# Copy_of_Archimedes_Islemci_Kat.net
KiCad netlist of a schematic drawn in Altium Designer
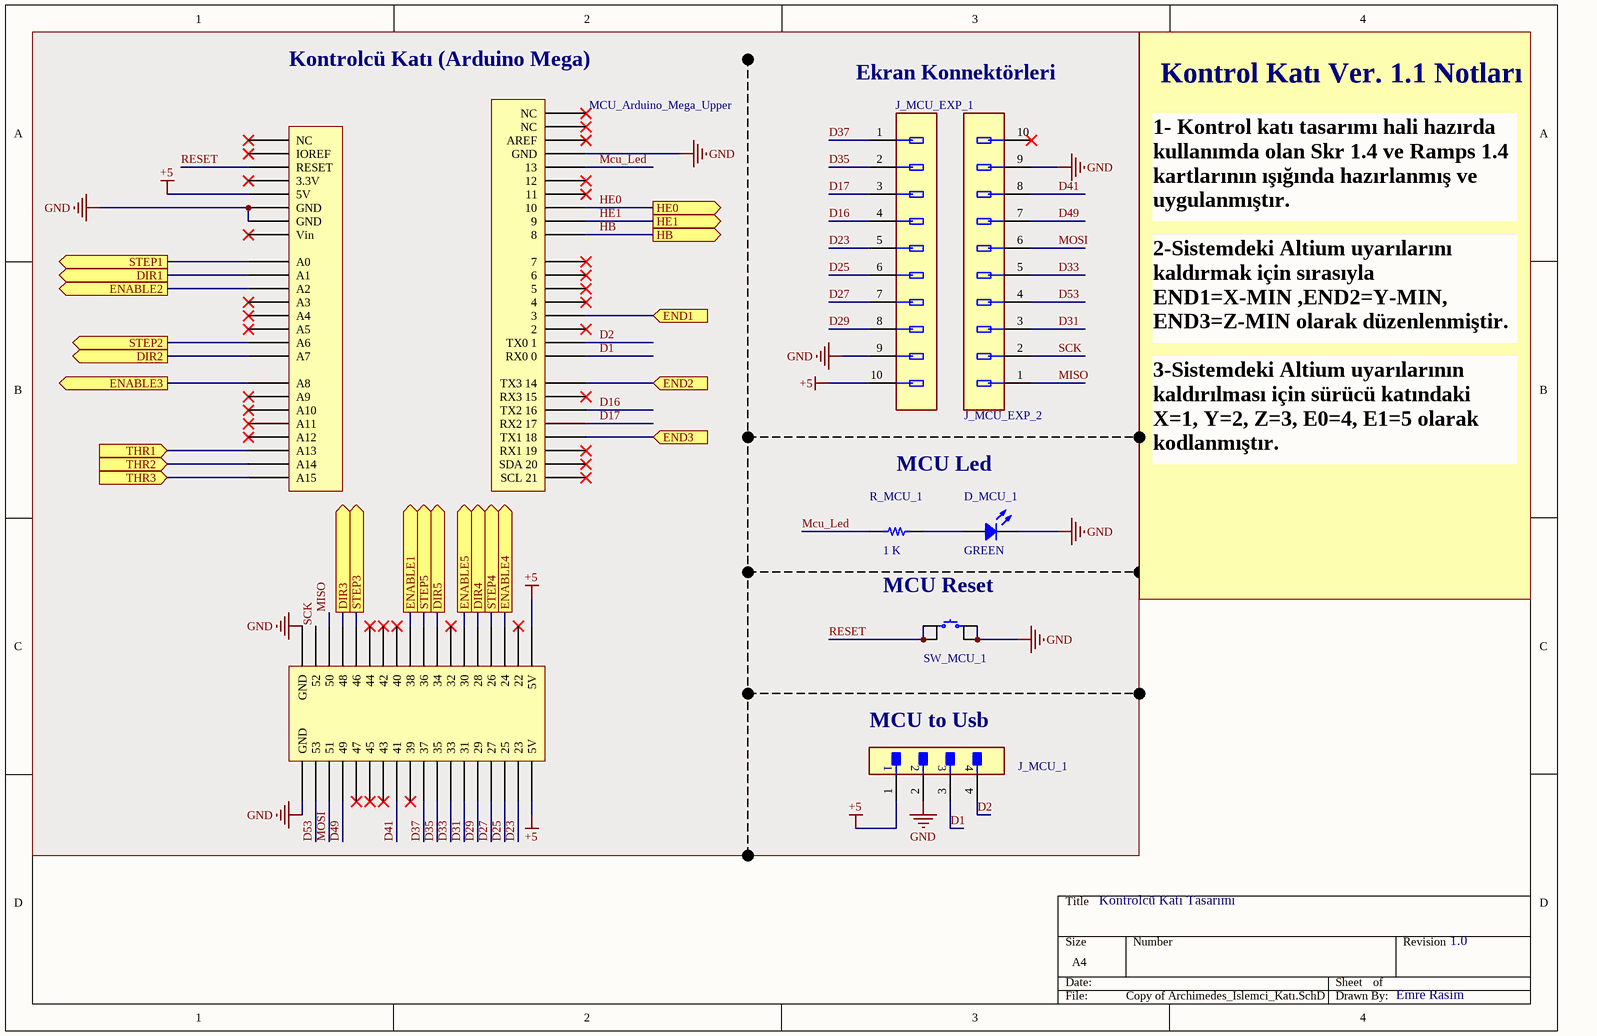
[diagram p0: Copy of Archimedes_Islemci_Katı.SchDoc]

(export (version "E")
  (design (tool "Eeschema 10.0.6"))
  (components
    (comp (ref "D_MCU_1")
      (value "GREEN")
      (footprint "LED 0805/2012 GREEN")
      (description "LED 805")
      (libsource (lib "Pasifler") (part "LED 805"))
    )
    (comp (ref "J_MCU_1")
      (value "2.5 mm locked")
      (footprint "CON_2.5MM_4_LEAD_180_LOCKED")
      (description "2.5 mm 4 lead locked connector")
      (libsource (lib "EKIM_Team_Main") (part "Con_2.5mm_4_lead_180_locked"))
    )
    (comp (ref "J_MCU_EXP_1")
      (value "Con_2.54mm_10 lead_2 row_Ipc connector")
      (footprint "Con_10pin_2row_ıpc_connector")
      (description "CONN 10 Positions Header Connector 0.100\" (2.54mm) Through Hole Gold")
      (fields (field (name "VOLTAGE") "250V") (field (name "MANUFACTURER") "Molex"))
      (libsource (lib "EKIM_Team_Main") (part "Con_2.54mm_10 lead_2 row_Ipc connector"))
    )
    (comp (ref "J_MCU_EXP_2")
      (value "Con_2.54mm_10 lead_2 row_Ipc connector")
      (footprint "Con_10pin_2row_ıpc_connector")
      (description "CONN 10 Positions Header Connector 0.100\" (2.54mm) Through Hole Gold")
      (fields (field (name "VOLTAGE") "250V") (field (name "MANUFACTURER") "Molex"))
      (libsource (lib "") (part "Con_2.54mm_10 lead_2 row_Ipc connector_1"))
    )
    (comp (ref "MCU_Arduino_Mega_Upper")
      (value "Arduino Mega 2560")
      (footprint "MCU_Arduino_MEGA_Upper")
      (libsource (lib "EKIM_Team_Main") (part "MCU_Arduino_Mega_Upper"))
    )
    (comp (ref "R_MCU_1")
      (value "1 K")
      (footprint "RES 0805/2012")
      (description "Resistor 805")
      (libsource (lib "Pasifler") (part "Resistor 805"))
    )
    (comp (ref "SW_MCU_1")
      (value "Push button with 6x6 landmark")
      (footprint "SW_PUSH_6X6mm")
      (libsource (lib "EKIM_Team_Main") (part "SW_PUSH_6X6mm"))
    )
  )
  (nets
    (net (code "1") (name "+5") (class "Default")
      (node (ref "J_MCU_1") (pin "1") (pinfunction "1_1") (pintype "passive"))
      (node (ref "J_MCU_EXP_1") (pin "10") (pinfunction "10_10") (pintype "passive"))
      (node (ref "MCU_Arduino_Mega_Upper") (pin "1") (pinfunction "5V_1") (pintype "passive"))
      (node (ref "MCU_Arduino_Mega_Upper") (pin "2") (pinfunction "5V_2") (pintype "passive"))
      (node (ref "MCU_Arduino_Mega_Upper") (pin "56") (pinfunction "5V_56") (pintype "passive"))
    )
    (net (code "2") (name "/D1") (class "Default")
      (node (ref "J_MCU_1") (pin "3") (pinfunction "3_3") (pintype "passive"))
      (node (ref "MCU_Arduino_Mega_Upper") (pin "69") (pinfunction "RX0_0_69") (pintype "passive"))
    )
    (net (code "3") (name "/D2") (class "Default")
      (node (ref "J_MCU_1") (pin "4") (pinfunction "4_4") (pintype "passive"))
      (node (ref "MCU_Arduino_Mega_Upper") (pin "70") (pinfunction "TX0_1_70") (pintype "passive"))
    )
    (net (code "4") (name "/D16") (class "Default")
      (node (ref "J_MCU_EXP_1") (pin "4") (pinfunction "4_4") (pintype "passive"))
      (node (ref "MCU_Arduino_Mega_Upper") (pin "66") (pinfunction "TX2_16_66") (pintype "passive"))
    )
    (net (code "5") (name "/D17") (class "Default")
      (node (ref "J_MCU_EXP_1") (pin "3") (pinfunction "3_3") (pintype "passive"))
      (node (ref "MCU_Arduino_Mega_Upper") (pin "65") (pinfunction "RX2_17_65") (pintype "passive"))
    )
    (net (code "6") (name "/D23") (class "Default")
      (node (ref "J_MCU_EXP_1") (pin "5") (pinfunction "5_5") (pintype "passive"))
      (node (ref "MCU_Arduino_Mega_Upper") (pin "4") (pinfunction "23_4") (pintype "passive"))
    )
    (net (code "7") (name "/D25") (class "Default")
      (node (ref "J_MCU_EXP_1") (pin "6") (pinfunction "6_6") (pintype "passive"))
      (node (ref "MCU_Arduino_Mega_Upper") (pin "6") (pinfunction "25_6") (pintype "passive"))
    )
    (net (code "8") (name "/D27") (class "Default")
      (node (ref "J_MCU_EXP_1") (pin "7") (pinfunction "7_7") (pintype "passive"))
      (node (ref "MCU_Arduino_Mega_Upper") (pin "8") (pinfunction "27_8") (pintype "passive"))
    )
    (net (code "9") (name "/D29") (class "Default")
      (node (ref "J_MCU_EXP_1") (pin "8") (pinfunction "8_8") (pintype "passive"))
      (node (ref "MCU_Arduino_Mega_Upper") (pin "10") (pinfunction "29_10") (pintype "passive"))
    )
    (net (code "10") (name "/D31") (class "Default")
      (node (ref "J_MCU_EXP_2") (pin "3") (pinfunction "3_3") (pintype "passive"))
      (node (ref "MCU_Arduino_Mega_Upper") (pin "12") (pinfunction "31_12") (pintype "passive"))
    )
    (net (code "11") (name "/D33") (class "Default")
      (node (ref "J_MCU_EXP_2") (pin "5") (pinfunction "5_5") (pintype "passive"))
      (node (ref "MCU_Arduino_Mega_Upper") (pin "14") (pinfunction "33_14") (pintype "passive"))
    )
    (net (code "12") (name "/D35") (class "Default")
      (node (ref "J_MCU_EXP_1") (pin "2") (pinfunction "2_2") (pintype "passive"))
      (node (ref "MCU_Arduino_Mega_Upper") (pin "16") (pinfunction "35_16") (pintype "passive"))
    )
    (net (code "13") (name "/D37") (class "Default")
      (node (ref "J_MCU_EXP_1") (pin "1") (pinfunction "1_1") (pintype "passive"))
      (node (ref "MCU_Arduino_Mega_Upper") (pin "18") (pinfunction "37_18") (pintype "passive"))
    )
    (net (code "14") (name "/D41") (class "Default")
      (node (ref "J_MCU_EXP_2") (pin "8") (pinfunction "8_8") (pintype "passive"))
      (node (ref "MCU_Arduino_Mega_Upper") (pin "22") (pinfunction "41_22") (pintype "passive"))
    )
    (net (code "15") (name "/D49") (class "Default")
      (node (ref "J_MCU_EXP_2") (pin "7") (pinfunction "7_7") (pintype "passive"))
      (node (ref "MCU_Arduino_Mega_Upper") (pin "30") (pinfunction "49_30") (pintype "passive"))
    )
    (net (code "16") (name "/D53") (class "Default")
      (node (ref "J_MCU_EXP_2") (pin "4") (pinfunction "4_4") (pintype "passive"))
      (node (ref "MCU_Arduino_Mega_Upper") (pin "34") (pinfunction "53_34") (pintype "passive"))
    )
    (net (code "17") (name "/DIR1") (class "Default")
      (node (ref "MCU_Arduino_Mega_Upper") (pin "51") (pinfunction "A1_51") (pintype "passive"))
    )
    (net (code "18") (name "/DIR2") (class "Default")
      (node (ref "MCU_Arduino_Mega_Upper") (pin "45") (pinfunction "A7_45") (pintype "passive"))
    )
    (net (code "19") (name "/DIR3") (class "Default")
      (node (ref "MCU_Arduino_Mega_Upper") (pin "29") (pinfunction "48_29") (pintype "passive"))
    )
    (net (code "20") (name "/DIR4") (class "Default")
      (node (ref "MCU_Arduino_Mega_Upper") (pin "9") (pinfunction "28_9") (pintype "passive"))
    )
    (net (code "21") (name "/DIR5") (class "Default")
      (node (ref "MCU_Arduino_Mega_Upper") (pin "15") (pinfunction "34_15") (pintype "passive"))
    )
    (net (code "22") (name "/ENABLE1") (class "Default")
      (node (ref "MCU_Arduino_Mega_Upper") (pin "19") (pinfunction "38_19") (pintype "passive"))
    )
    (net (code "23") (name "/ENABLE2") (class "Default")
      (node (ref "MCU_Arduino_Mega_Upper") (pin "50") (pinfunction "A2_50") (pintype "passive"))
    )
    (net (code "24") (name "/ENABLE3") (class "Default")
      (node (ref "MCU_Arduino_Mega_Upper") (pin "44") (pinfunction "A8_44") (pintype "passive"))
    )
    (net (code "25") (name "/ENABLE4") (class "Default")
      (node (ref "MCU_Arduino_Mega_Upper") (pin "5") (pinfunction "24_5") (pintype "passive"))
    )
    (net (code "26") (name "/ENABLE5") (class "Default")
      (node (ref "MCU_Arduino_Mega_Upper") (pin "11") (pinfunction "30_11") (pintype "passive"))
    )
    (net (code "27") (name "/END1") (class "Default")
      (node (ref "MCU_Arduino_Mega_Upper") (pin "72") (pinfunction "3_72") (pintype "passive"))
    )
    (net (code "28") (name "/END2") (class "Default")
      (node (ref "MCU_Arduino_Mega_Upper") (pin "68") (pinfunction "TX3_14_68") (pintype "passive"))
    )
    (net (code "29") (name "/END3") (class "Default")
      (node (ref "MCU_Arduino_Mega_Upper") (pin "64") (pinfunction "TX1_18_64") (pintype "passive"))
    )
    (net (code "30") (name "/HB") (class "Default")
      (node (ref "MCU_Arduino_Mega_Upper") (pin "77") (pinfunction "8_77") (pintype "passive"))
    )
    (net (code "31") (name "/HE0") (class "Default")
      (node (ref "MCU_Arduino_Mega_Upper") (pin "79") (pinfunction "10_79") (pintype "passive"))
    )
    (net (code "32") (name "/HE1") (class "Default")
      (node (ref "MCU_Arduino_Mega_Upper") (pin "78") (pinfunction "9_78") (pintype "passive"))
    )
    (net (code "33") (name "/MISO") (class "Default")
      (node (ref "J_MCU_EXP_2") (pin "1") (pinfunction "1_1") (pintype "passive"))
      (node (ref "MCU_Arduino_Mega_Upper") (pin "31") (pinfunction "50_31") (pintype "passive"))
    )
    (net (code "34") (name "/MOSI") (class "Default")
      (node (ref "J_MCU_EXP_2") (pin "6") (pinfunction "6_6") (pintype "passive"))
      (node (ref "MCU_Arduino_Mega_Upper") (pin "32") (pinfunction "51_32") (pintype "passive"))
    )
    (net (code "35") (name "/Mcu_Led") (class "Default")
      (node (ref "MCU_Arduino_Mega_Upper") (pin "82") (pinfunction "13_82") (pintype "passive"))
      (node (ref "R_MCU_1") (pin "1") (pinfunction "1_1") (pintype "passive"))
    )
    (net (code "36") (name "/RESET") (class "Default")
      (node (ref "MCU_Arduino_Mega_Upper") (pin "58") (pinfunction "RESET_58") (pintype "passive"))
      (node (ref "SW_MCU_1") (pin "1") (pinfunction "1_1") (pintype "passive"))
      (node (ref "SW_MCU_1") (pin "2") (pinfunction "2_2") (pintype "passive"))
    )
    (net (code "37") (name "/SCK") (class "Default")
      (node (ref "J_MCU_EXP_2") (pin "2") (pinfunction "2_2") (pintype "passive"))
      (node (ref "MCU_Arduino_Mega_Upper") (pin "33") (pinfunction "52_33") (pintype "passive"))
    )
    (net (code "38") (name "/STEP1") (class "Default")
      (node (ref "MCU_Arduino_Mega_Upper") (pin "52") (pinfunction "A0_52") (pintype "passive"))
    )
    (net (code "39") (name "/STEP2") (class "Default")
      (node (ref "MCU_Arduino_Mega_Upper") (pin "46") (pinfunction "A6_46") (pintype "passive"))
    )
    (net (code "40") (name "/STEP3") (class "Default")
      (node (ref "MCU_Arduino_Mega_Upper") (pin "27") (pinfunction "46_27") (pintype "passive"))
    )
    (net (code "41") (name "/STEP4") (class "Default")
      (node (ref "MCU_Arduino_Mega_Upper") (pin "7") (pinfunction "26_7") (pintype "passive"))
    )
    (net (code "42") (name "/STEP5") (class "Default")
      (node (ref "MCU_Arduino_Mega_Upper") (pin "17") (pinfunction "36_17") (pintype "passive"))
    )
    (net (code "43") (name "/THR1") (class "Default")
      (node (ref "MCU_Arduino_Mega_Upper") (pin "39") (pinfunction "A13_39") (pintype "passive"))
    )
    (net (code "44") (name "/THR2") (class "Default")
      (node (ref "MCU_Arduino_Mega_Upper") (pin "38") (pinfunction "A14_38") (pintype "passive"))
    )
    (net (code "45") (name "/THR3") (class "Default")
      (node (ref "MCU_Arduino_Mega_Upper") (pin "37") (pinfunction "A15_37") (pintype "passive"))
    )
    (net (code "46") (name "GND") (class "Default")
      (node (ref "D_MCU_1") (pin "2") (pinfunction "2_2") (pintype "passive"))
      (node (ref "J_MCU_1") (pin "2") (pinfunction "2_2") (pintype "passive"))
      (node (ref "J_MCU_EXP_1") (pin "9") (pinfunction "9_9") (pintype "passive"))
      (node (ref "J_MCU_EXP_2") (pin "9") (pinfunction "9_9") (pintype "passive"))
      (node (ref "MCU_Arduino_Mega_Upper") (pin "35") (pinfunction "GND_35") (pintype "passive"))
      (node (ref "MCU_Arduino_Mega_Upper") (pin "36") (pinfunction "GND_36") (pintype "passive"))
      (node (ref "MCU_Arduino_Mega_Upper") (pin "54") (pinfunction "GND_54") (pintype "passive"))
      (node (ref "MCU_Arduino_Mega_Upper") (pin "55") (pinfunction "GND_55") (pintype "passive"))
      (node (ref "MCU_Arduino_Mega_Upper") (pin "83") (pinfunction "GND_83") (pintype "passive"))
      (node (ref "SW_MCU_1") (pin "3") (pinfunction "3_3") (pintype "passive"))
      (node (ref "SW_MCU_1") (pin "4") (pinfunction "4_4") (pintype "passive"))
    )
    (net (code "47") (name "Net-(D_MCU_1-Pad1)") (class "Default")
      (node (ref "D_MCU_1") (pin "1") (pinfunction "1_1") (pintype "passive"))
      (node (ref "R_MCU_1") (pin "2") (pinfunction "2_2") (pintype "passive"))
    )
    (net (code "48") (name "unconnected-(J_MCU_EXP_2-Pad10)") (class "Default")
      (node (ref "J_MCU_EXP_2") (pin "10") (pinfunction "10_10") (pintype "passive+no_connect"))
    )
    (net (code "49") (name "unconnected-(MCU_Arduino_Mega_Upper-2-Pad71)") (class "Default")
      (node (ref "MCU_Arduino_Mega_Upper") (pin "71") (pinfunction "2_71") (pintype "passive+no_connect"))
    )
    (net (code "50") (name "unconnected-(MCU_Arduino_Mega_Upper-3.3V-Pad57)") (class "Default")
      (node (ref "MCU_Arduino_Mega_Upper") (pin "57") (pinfunction "3.3V_57") (pintype "passive+no_connect"))
    )
    (net (code "51") (name "unconnected-(MCU_Arduino_Mega_Upper-4-Pad73)") (class "Default")
      (node (ref "MCU_Arduino_Mega_Upper") (pin "73") (pinfunction "4_73") (pintype "passive+no_connect"))
    )
    (net (code "52") (name "unconnected-(MCU_Arduino_Mega_Upper-5-Pad74)") (class "Default")
      (node (ref "MCU_Arduino_Mega_Upper") (pin "74") (pinfunction "5_74") (pintype "passive+no_connect"))
    )
    (net (code "53") (name "unconnected-(MCU_Arduino_Mega_Upper-6-Pad75)") (class "Default")
      (node (ref "MCU_Arduino_Mega_Upper") (pin "75") (pinfunction "6_75") (pintype "passive+no_connect"))
    )
    (net (code "54") (name "unconnected-(MCU_Arduino_Mega_Upper-7-Pad76)") (class "Default")
      (node (ref "MCU_Arduino_Mega_Upper") (pin "76") (pinfunction "7_76") (pintype "passive+no_connect"))
    )
    (net (code "55") (name "unconnected-(MCU_Arduino_Mega_Upper-11-Pad80)") (class "Default")
      (node (ref "MCU_Arduino_Mega_Upper") (pin "80") (pinfunction "11_80") (pintype "passive+no_connect"))
    )
    (net (code "56") (name "unconnected-(MCU_Arduino_Mega_Upper-12-Pad81)") (class "Default")
      (node (ref "MCU_Arduino_Mega_Upper") (pin "81") (pinfunction "12_81") (pintype "passive+no_connect"))
    )
    (net (code "57") (name "unconnected-(MCU_Arduino_Mega_Upper-22-Pad3)") (class "Default")
      (node (ref "MCU_Arduino_Mega_Upper") (pin "3") (pinfunction "22_3") (pintype "passive+no_connect"))
    )
    (net (code "58") (name "unconnected-(MCU_Arduino_Mega_Upper-32-Pad13)") (class "Default")
      (node (ref "MCU_Arduino_Mega_Upper") (pin "13") (pinfunction "32_13") (pintype "passive+no_connect"))
    )
    (net (code "59") (name "unconnected-(MCU_Arduino_Mega_Upper-39-Pad20)") (class "Default")
      (node (ref "MCU_Arduino_Mega_Upper") (pin "20") (pinfunction "39_20") (pintype "passive+no_connect"))
    )
    (net (code "60") (name "unconnected-(MCU_Arduino_Mega_Upper-40-Pad21)") (class "Default")
      (node (ref "MCU_Arduino_Mega_Upper") (pin "21") (pinfunction "40_21") (pintype "passive+no_connect"))
    )
    (net (code "61") (name "unconnected-(MCU_Arduino_Mega_Upper-42-Pad23)") (class "Default")
      (node (ref "MCU_Arduino_Mega_Upper") (pin "23") (pinfunction "42_23") (pintype "passive+no_connect"))
    )
    (net (code "62") (name "unconnected-(MCU_Arduino_Mega_Upper-43-Pad24)") (class "Default")
      (node (ref "MCU_Arduino_Mega_Upper") (pin "24") (pinfunction "43_24") (pintype "passive+no_connect"))
    )
    (net (code "63") (name "unconnected-(MCU_Arduino_Mega_Upper-44-Pad25)") (class "Default")
      (node (ref "MCU_Arduino_Mega_Upper") (pin "25") (pinfunction "44_25") (pintype "passive+no_connect"))
    )
    (net (code "64") (name "unconnected-(MCU_Arduino_Mega_Upper-45-Pad26)") (class "Default")
      (node (ref "MCU_Arduino_Mega_Upper") (pin "26") (pinfunction "45_26") (pintype "passive+no_connect"))
    )
    (net (code "65") (name "unconnected-(MCU_Arduino_Mega_Upper-47-Pad28)") (class "Default")
      (node (ref "MCU_Arduino_Mega_Upper") (pin "28") (pinfunction "47_28") (pintype "passive+no_connect"))
    )
    (net (code "66") (name "unconnected-(MCU_Arduino_Mega_Upper-A3-Pad49)") (class "Default")
      (node (ref "MCU_Arduino_Mega_Upper") (pin "49") (pinfunction "A3_49") (pintype "passive+no_connect"))
    )
    (net (code "67") (name "unconnected-(MCU_Arduino_Mega_Upper-A4-Pad48)") (class "Default")
      (node (ref "MCU_Arduino_Mega_Upper") (pin "48") (pinfunction "A4_48") (pintype "passive+no_connect"))
    )
    (net (code "68") (name "unconnected-(MCU_Arduino_Mega_Upper-A5-Pad47)") (class "Default")
      (node (ref "MCU_Arduino_Mega_Upper") (pin "47") (pinfunction "A5_47") (pintype "passive+no_connect"))
    )
    (net (code "69") (name "unconnected-(MCU_Arduino_Mega_Upper-A9-Pad43)") (class "Default")
      (node (ref "MCU_Arduino_Mega_Upper") (pin "43") (pinfunction "A9_43") (pintype "passive+no_connect"))
    )
    (net (code "70") (name "unconnected-(MCU_Arduino_Mega_Upper-A10-Pad42)") (class "Default")
      (node (ref "MCU_Arduino_Mega_Upper") (pin "42") (pinfunction "A10_42") (pintype "passive+no_connect"))
    )
    (net (code "71") (name "unconnected-(MCU_Arduino_Mega_Upper-A11-Pad41)") (class "Default")
      (node (ref "MCU_Arduino_Mega_Upper") (pin "41") (pinfunction "A11_41") (pintype "passive+no_connect"))
    )
    (net (code "72") (name "unconnected-(MCU_Arduino_Mega_Upper-A12-Pad40)") (class "Default")
      (node (ref "MCU_Arduino_Mega_Upper") (pin "40") (pinfunction "A12_40") (pintype "passive+no_connect"))
    )
    (net (code "73") (name "unconnected-(MCU_Arduino_Mega_Upper-AREF-Pad84)") (class "Default")
      (node (ref "MCU_Arduino_Mega_Upper") (pin "84") (pinfunction "AREF_84") (pintype "passive+no_connect"))
    )
    (net (code "74") (name "unconnected-(MCU_Arduino_Mega_Upper-IOREF-Pad59)") (class "Default")
      (node (ref "MCU_Arduino_Mega_Upper") (pin "59") (pinfunction "IOREF_59") (pintype "passive+no_connect"))
    )
    (net (code "75") (name "unconnected-(MCU_Arduino_Mega_Upper-NC-Pad60)") (class "Default")
      (node (ref "MCU_Arduino_Mega_Upper") (pin "60") (pinfunction "NC_60") (pintype "passive+no_connect"))
    )
    (net (code "76") (name "unconnected-(MCU_Arduino_Mega_Upper-NC-Pad85)") (class "Default")
      (node (ref "MCU_Arduino_Mega_Upper") (pin "85") (pinfunction "NC_85") (pintype "passive+no_connect"))
    )
    (net (code "77") (name "unconnected-(MCU_Arduino_Mega_Upper-NC-Pad86)") (class "Default")
      (node (ref "MCU_Arduino_Mega_Upper") (pin "86") (pinfunction "NC_86") (pintype "passive+no_connect"))
    )
    (net (code "78") (name "unconnected-(MCU_Arduino_Mega_Upper-RX1_19-Pad63)") (class "Default")
      (node (ref "MCU_Arduino_Mega_Upper") (pin "63") (pinfunction "RX1_19_63") (pintype "passive+no_connect"))
    )
    (net (code "79") (name "unconnected-(MCU_Arduino_Mega_Upper-RX3_15-Pad67)") (class "Default")
      (node (ref "MCU_Arduino_Mega_Upper") (pin "67") (pinfunction "RX3_15_67") (pintype "passive+no_connect"))
    )
    (net (code "80") (name "unconnected-(MCU_Arduino_Mega_Upper-SCL_21-Pad61)") (class "Default")
      (node (ref "MCU_Arduino_Mega_Upper") (pin "61") (pinfunction "SCL_21_61") (pintype "passive+no_connect"))
    )
    (net (code "81") (name "unconnected-(MCU_Arduino_Mega_Upper-SDA_20-Pad62)") (class "Default")
      (node (ref "MCU_Arduino_Mega_Upper") (pin "62") (pinfunction "SDA_20_62") (pintype "passive+no_connect"))
    )
    (net (code "82") (name "unconnected-(MCU_Arduino_Mega_Upper-Vin-Pad53)") (class "Default")
      (node (ref "MCU_Arduino_Mega_Upper") (pin "53") (pinfunction "Vin_53") (pintype "passive+no_connect"))
    )
  )
)
